# Ethernet_PHY.net
KiCad netlist of a schematic drawn in Altium Designer
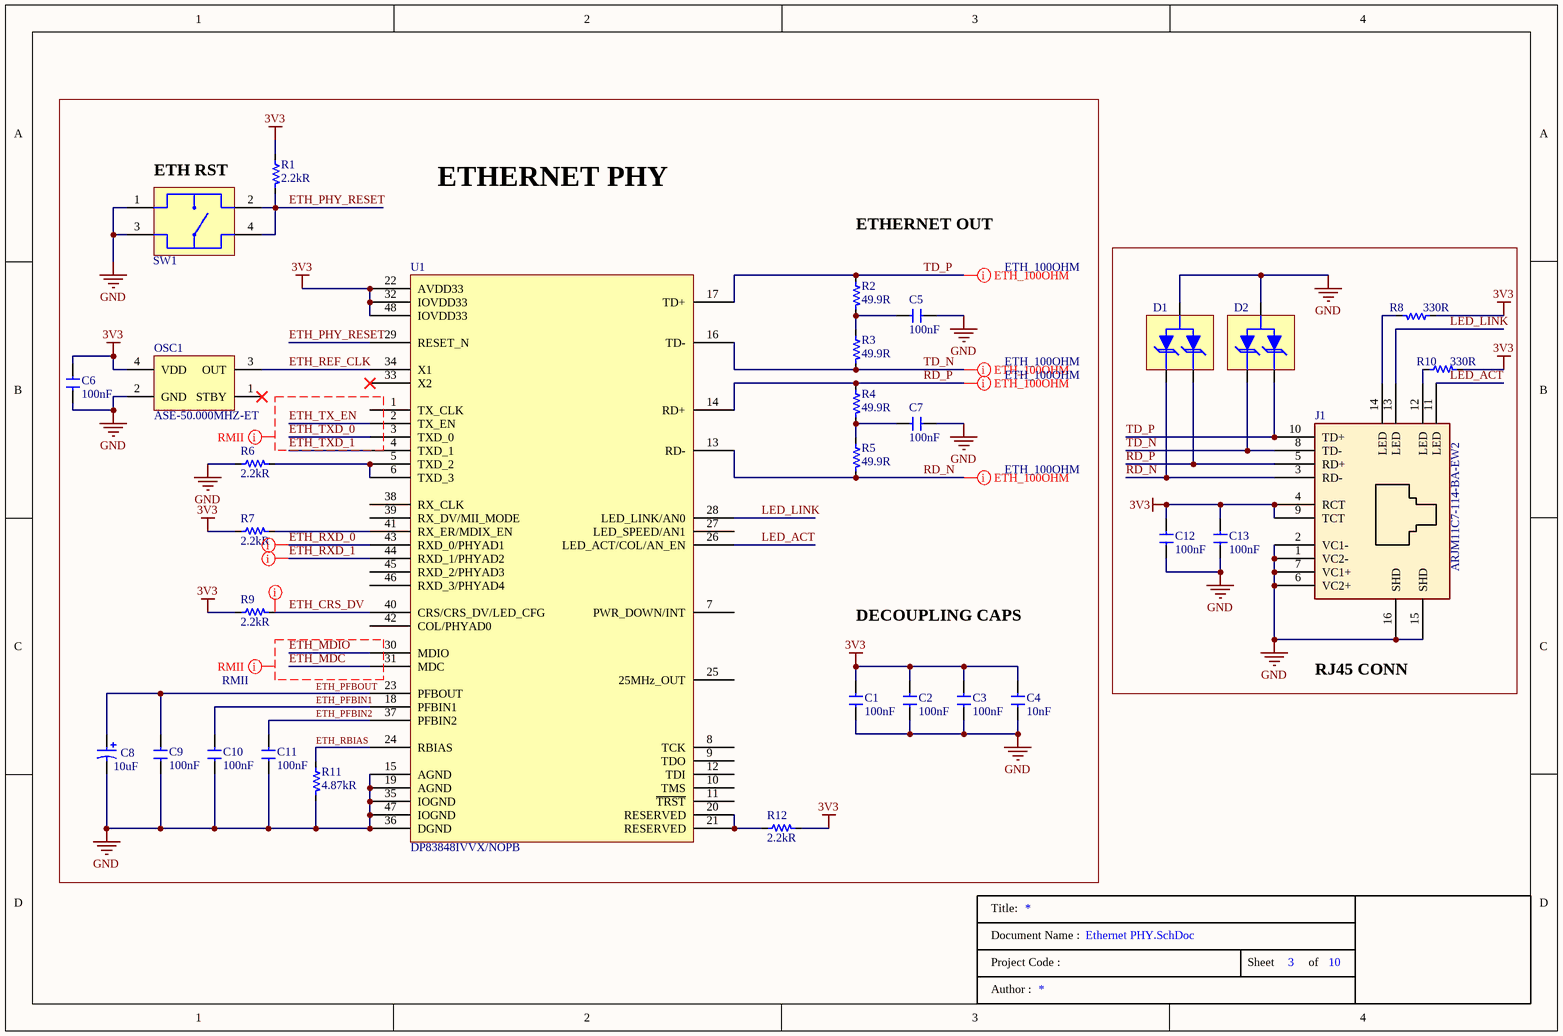
[diagram p0: Ethernet PHY.SchDoc]

(export (version "E")
  (design (tool "Eeschema 10.0.6"))
  (components
    (comp (ref "C1")
      (value "CAP_0.1uF_%20_50V_0805_X7R_CER")
      (footprint "0805_CAP")
      (description "Cap Ceramic 0.1uF 50V X7R 20% SMD 0805 125C Paper T/R")
      (fields
        (field (name "MANUFACTURER") "KEMET")
        (field (name "MANUFACTURER PART NUMBER") "C0805C104M5RACTU")
        (field (name "CAPACITANCE") "100nF")
      )
      (libsource (lib "Main Schematic Library") (part "CAP_0.1uF_%20_50V_0805_X7R_CER"))
    )
    (comp (ref "C2")
      (value "CAP_0.1uF_%20_50V_0805_X7R_CER")
      (footprint "0805_CAP")
      (description "Cap Ceramic 0.1uF 50V X7R 20% SMD 0805 125C Paper T/R")
      (fields
        (field (name "MANUFACTURER") "KEMET")
        (field (name "MANUFACTURER PART NUMBER") "C0805C104M5RACTU")
        (field (name "CAPACITANCE") "100nF")
      )
      (libsource (lib "Main Schematic Library") (part "CAP_0.1uF_%20_50V_0805_X7R_CER"))
    )
    (comp (ref "C3")
      (value "CAP_0.1uF_%20_50V_0805_X7R_CER")
      (footprint "0805_CAP")
      (description "Cap Ceramic 0.1uF 50V X7R 20% SMD 0805 125C Paper T/R")
      (fields
        (field (name "MANUFACTURER") "KEMET")
        (field (name "MANUFACTURER PART NUMBER") "C0805C104M5RACTU")
        (field (name "CAPACITANCE") "100nF")
      )
      (libsource (lib "Main Schematic Library") (part "CAP_0.1uF_%20_50V_0805_X7R_CER"))
    )
    (comp (ref "C4")
      (value "CAP_10nF_%10_50V_0805_X7R_CER")
      (footprint "0805_CAP")
      (description "CAP CER 10000PF 50V X7R 0805")
      (fields
        (field (name "MANUFACTURER") "Samsung")
        (field (name "MANUFACTURER PART NUMBER") "CL21B103KBANNNC")
        (field (name "CAPACITANCE") "10nF")
      )
      (libsource (lib "Main Schematic Library") (part "CAP_10nF_%10_50V_0805_X7R_CER"))
    )
    (comp (ref "C5")
      (value "CAP_0.1uF_50V_0805_X7R_CER")
      (footprint "0805_CAP")
      (description "Cap Ceramic 0.1uF 50V X7R 20% SMD 0805 125C Paper T/R")
      (fields
        (field (name "MANUFACTURER") "KEMET")
        (field (name "MANUFACTURER PART NUMBER") "C0805C104M5RACTU")
        (field (name "CAPACITANCE") "100nF")
      )
      (libsource (lib "Main Component Library") (part "CAP_0.1uF_50V_0805_X7R_CER"))
    )
    (comp (ref "C6")
      (value "CAP_0.1uF_50V_0805_X7R_CER")
      (footprint "0805_CAP")
      (description "Cap Ceramic 0.1uF 50V X7R 20% SMD 0805 125C Paper T/R")
      (fields
        (field (name "MANUFACTURER") "KEMET")
        (field (name "MANUFACTURER PART NUMBER") "C0805C104M5RACTU")
        (field (name "CAPACITANCE") "100nF")
      )
      (libsource (lib "Main Component Library") (part "CAP_0.1uF_50V_0805_X7R_CER"))
    )
    (comp (ref "C7")
      (value "CAP_0.1uF_50V_0805_X7R_CER")
      (footprint "0805_CAP")
      (description "Cap Ceramic 0.1uF 50V X7R 20% SMD 0805 125C Paper T/R")
      (fields
        (field (name "MANUFACTURER") "KEMET")
        (field (name "MANUFACTURER PART NUMBER") "C0805C104M5RACTU")
        (field (name "CAPACITANCE") "100nF")
      )
      (libsource (lib "Main Component Library") (part "CAP_0.1uF_50V_0805_X7R_CER"))
    )
    (comp (ref "C8")
      (value "CAP_10uF_10V_10%_1206_TANT")
      (footprint "1206_TANT_CAP")
      (description "Cap Tant Solid 10uF 10V A CASE 10% (3.2 X 1.6 X 1.6mm) Inward L SMD 3216-18 3 Ohm 125C T/R")
      (fields
        (field (name "MANUFACTURER") "Kyocera AVX")
        (field (name "MANUFACTURER PART NUMBER") "TAJA106K010SNJ")
        (field (name "CAPACITANCE") "10uF")
      )
      (libsource (lib "Main Component Library") (part "CAP_10uF_10V_10%_1206_TANT"))
    )
    (comp (ref "C9")
      (value "CAP_0.1uF_%20_50V_0805_X7R_CER")
      (footprint "0805_CAP")
      (description "Cap Ceramic 0.1uF 50V X7R 20% SMD 0805 125C Paper T/R")
      (fields
        (field (name "MANUFACTURER") "KEMET")
        (field (name "MANUFACTURER PART NUMBER") "C0805C104M5RACTU")
        (field (name "CAPACITANCE") "100nF")
      )
      (libsource (lib "Main Schematic Library") (part "CAP_0.1uF_%20_50V_0805_X7R_CER"))
    )
    (comp (ref "C10")
      (value "CAP_0.1uF_%20_50V_0805_X7R_CER")
      (footprint "0805_CAP")
      (description "Cap Ceramic 0.1uF 50V X7R 20% SMD 0805 125C Paper T/R")
      (fields
        (field (name "MANUFACTURER") "KEMET")
        (field (name "MANUFACTURER PART NUMBER") "C0805C104M5RACTU")
        (field (name "CAPACITANCE") "100nF")
      )
      (libsource (lib "Main Schematic Library") (part "CAP_0.1uF_%20_50V_0805_X7R_CER"))
    )
    (comp (ref "C11")
      (value "CAP_0.1uF_%20_50V_0805_X7R_CER")
      (footprint "0805_CAP")
      (description "Cap Ceramic 0.1uF 50V X7R 20% SMD 0805 125C Paper T/R")
      (fields
        (field (name "MANUFACTURER") "KEMET")
        (field (name "MANUFACTURER PART NUMBER") "C0805C104M5RACTU")
        (field (name "CAPACITANCE") "100nF")
      )
      (libsource (lib "Main Schematic Library") (part "CAP_0.1uF_%20_50V_0805_X7R_CER"))
    )
    (comp (ref "C12")
      (value "CAP_0.1uF_50V_0805_X7R_CER")
      (footprint "0805_CAP")
      (description "Cap Ceramic 0.1uF 50V X7R 20% SMD 0805 125C Paper T/R")
      (fields
        (field (name "MANUFACTURER") "KEMET")
        (field (name "MANUFACTURER PART NUMBER") "C0805C104M5RACTU")
        (field (name "CAPACITANCE") "100nF")
      )
      (libsource (lib "Main Component Library") (part "CAP_0.1uF_50V_0805_X7R_CER"))
    )
    (comp (ref "C13")
      (value "CAP_0.1uF_50V_0805_X7R_CER")
      (footprint "0805_CAP")
      (description "Cap Ceramic 0.1uF 50V X7R 20% SMD 0805 125C Paper T/R")
      (fields
        (field (name "MANUFACTURER") "KEMET")
        (field (name "MANUFACTURER PART NUMBER") "C0805C104M5RACTU")
        (field (name "CAPACITANCE") "100nF")
      )
      (libsource (lib "Main Component Library") (part "CAP_0.1uF_50V_0805_X7R_CER"))
    )
    (comp (ref "D1")
      (value "DIODE_TVS_3.3VWM_8VC_SOT23")
      (footprint "SOT170P237X110-3N")
      (description "ESD Suppressor TVS Uni-Dir 3.3V 3-Pin SOT-23 T/R")
      (fields (field (name "MANUFACTURER") "MCC") (field (name "MANUFACTURER PART NUMBER") "ESD3V3AP-TP"))
      (libsource (lib "Main Schematic Library") (part "DIODE_TVS_3.3VWM_8VC_SOT23"))
    )
    (comp (ref "D2")
      (value "DIODE_TVS_3.3VWM_8VC_SOT23")
      (footprint "SOT170P237X110-3N")
      (description "ESD Suppressor TVS Uni-Dir 3.3V 3-Pin SOT-23 T/R")
      (fields (field (name "MANUFACTURER") "MCC") (field (name "MANUFACTURER PART NUMBER") "ESD3V3AP-TP"))
      (libsource (lib "Main Schematic Library") (part "DIODE_TVS_3.3VWM_8VC_SOT23"))
    )
    (comp (ref "J1")
      (value "ARJM11C7-114-BA-EW2")
      (footprint "ARJM11C7-114-BA-EW2_ABR")
      (description "Conn RJ-45 F 8 POS 1.27mm Solder RA Thru-Hole 14 Terminal 1 Port Tray")
      (fields (field (name "MANUFACTURER") "Abracon"))
      (libsource (lib "Main Schematic Library") (part "CONN_RJ-45_JACK_1PORT 100 BASE-T PoE_w/LED"))
    )
    (comp (ref "OSC1")
      (value "ASE-50.000MHZ-ET")
      (footprint "4-SMD_CMOS_OSC_3.20MMX2.50")
      (description "3.2 X 2.5 X 1.1Mm, 3.3V , 100Ppm -20+70C, Smd Ceramic Oscillator Rohs Compliant: Yes")
      (fields (field (name "MANUFACTURER") "Abracon"))
      (libsource (lib "Main Component Library") (part "XTAL_OSC_XO_50.0000MHZ_CMOS_SMD"))
    )
    (comp (ref "R1")
      (value "RES_2.2K OHM_1%_0805_1/8W")
      (footprint "0805_RES")
      (description "Res Thick Film 0805 2.2K Ohm 1% 1/8W ±100ppm/°C SMD Paper T/R")
      (fields
        (field (name "MANUFACTURER") "Yageo")
        (field (name "MANUFACTURER PART NUMBER") "RC0805FR-132K2L")
        (field (name "RESISTANCE") "2.2kR")
      )
      (libsource (lib "Main Component Library") (part "RES_2.2K OHM_1%_0805_1/8W"))
    )
    (comp (ref "R2")
      (value "RES_49.9 OHM_1%_0603_1/10W")
      (footprint "0603_RES")
      (description "Res Thick Film 0603 49.9 Ohm 1% 1/10W ±100ppm/°C Molded SMD Paper T/R")
      (fields
        (field (name "MANUFACTURER") "Vishay")
        (field (name "MANUFACTURER PART NUMBER") "CRCW060349R9FKEAC")
        (field (name "RESISTANCE") "49.9R")
      )
      (libsource (lib "Main Component Library") (part "RES_49.9 OHM_1%_0603_1/10W"))
    )
    (comp (ref "R3")
      (value "RES_49.9 OHM_1%_0603_1/10W")
      (footprint "0603_RES")
      (description "Res Thick Film 0603 49.9 Ohm 1% 1/10W ±100ppm/°C Molded SMD Paper T/R")
      (fields
        (field (name "MANUFACTURER") "Vishay")
        (field (name "MANUFACTURER PART NUMBER") "CRCW060349R9FKEAC")
        (field (name "RESISTANCE") "49.9R")
      )
      (libsource (lib "Main Component Library") (part "RES_49.9 OHM_1%_0603_1/10W"))
    )
    (comp (ref "R4")
      (value "RES_49.9 OHM_1%_0603_1/10W")
      (footprint "0603_RES")
      (description "Res Thick Film 0603 49.9 Ohm 1% 1/10W ±100ppm/°C Molded SMD Paper T/R")
      (fields
        (field (name "MANUFACTURER") "Vishay")
        (field (name "MANUFACTURER PART NUMBER") "CRCW060349R9FKEAC")
        (field (name "RESISTANCE") "49.9R")
      )
      (libsource (lib "Main Component Library") (part "RES_49.9 OHM_1%_0603_1/10W"))
    )
    (comp (ref "R5")
      (value "RES_49.9 OHM_1%_0603_1/10W")
      (footprint "0603_RES")
      (description "Res Thick Film 0603 49.9 Ohm 1% 1/10W ±100ppm/°C Molded SMD Paper T/R")
      (fields
        (field (name "MANUFACTURER") "Vishay")
        (field (name "MANUFACTURER PART NUMBER") "CRCW060349R9FKEAC")
        (field (name "RESISTANCE") "49.9R")
      )
      (libsource (lib "Main Component Library") (part "RES_49.9 OHM_1%_0603_1/10W"))
    )
    (comp (ref "R6")
      (value "RES_2.2K OHM_1%_0805_1/8W")
      (footprint "0805_RES")
      (description "Res Thick Film 0805 2.2K Ohm 1% 1/8W ±100ppm/°C SMD Paper T/R")
      (fields
        (field (name "MANUFACTURER") "Yageo")
        (field (name "MANUFACTURER PART NUMBER") "RC0805FR-132K2L")
        (field (name "RESISTANCE") "2.2kR")
      )
      (libsource (lib "Main Component Library") (part "RES_2.2K OHM_1%_0805_1/8W"))
    )
    (comp (ref "R7")
      (value "RES_2.2K OHM_1%_0805_1/8W")
      (footprint "0805_RES")
      (description "Res Thick Film 0805 2.2K Ohm 1% 1/8W ±100ppm/°C SMD Paper T/R")
      (fields
        (field (name "MANUFACTURER") "Yageo")
        (field (name "MANUFACTURER PART NUMBER") "RC0805FR-132K2L")
        (field (name "RESISTANCE") "2.2kR")
      )
      (libsource (lib "Main Component Library") (part "RES_2.2K OHM_1%_0805_1/8W"))
    )
    (comp (ref "R8")
      (value "RES_330 OHM_5%_0805_1/8W")
      (footprint "0805_RES")
      (description "Res Thick Film 0805 330 Ohm 5% 0.125W(1/8W) ±100ppm/C Pad SMD Automotive T/R")
      (fields
        (field (name "MANUFACTURER") "TE Connectivity")
        (field (name "MANUFACTURER PART NUMBER") "CRGCQ0805J330R")
        (field (name "RESISTANCE") "330R")
      )
      (libsource (lib "Main Component Library") (part "RES_330 OHM_5%_0805_1/8W"))
    )
    (comp (ref "R9")
      (value "RES_2.2K OHM_1%_0805_1/8W")
      (footprint "0805_RES")
      (description "Res Thick Film 0805 2.2K Ohm 1% 1/8W ±100ppm/°C SMD Paper T/R")
      (fields
        (field (name "MANUFACTURER") "Yageo")
        (field (name "MANUFACTURER PART NUMBER") "RC0805FR-132K2L")
        (field (name "RESISTANCE") "2.2kR")
      )
      (libsource (lib "Main Component Library") (part "RES_2.2K OHM_1%_0805_1/8W"))
    )
    (comp (ref "R10")
      (value "RES_330 OHM_5%_0805_1/8W")
      (footprint "0805_RES")
      (description "Res Thick Film 0805 330 Ohm 5% 0.125W(1/8W) ±100ppm/C Pad SMD Automotive T/R")
      (fields
        (field (name "MANUFACTURER") "TE Connectivity")
        (field (name "MANUFACTURER PART NUMBER") "CRGCQ0805J330R")
        (field (name "RESISTANCE") "330R")
      )
      (libsource (lib "Main Component Library") (part "RES_330 OHM_5%_0805_1/8W"))
    )
    (comp (ref "R11")
      (value "RES_4.87K_OHM_1%_1/8W 0805")
      (footprint "0805_RES")
      (description "Res Thick Film 0805 4.87K Ohm 1% 1/8W ±100ppm/°C SMD Paper T/R")
      (fields
        (field (name "MANUFACTURER") "Yageo")
        (field (name "MANUFACTURER PART NUMBER") "RC0805FR-074K87L")
        (field (name "RESISTANCE") "4.87kR")
      )
      (libsource (lib "Main Schematic Library") (part "RES_4.87K_OHM_1%_1/8W 0805"))
    )
    (comp (ref "R12")
      (value "RES_2.2K OHM_1%_0805_1/8W")
      (footprint "0805_RES")
      (description "Res Thick Film 0805 2.2K Ohm 1% 1/8W ±100ppm/°C SMD Paper T/R")
      (fields
        (field (name "MANUFACTURER") "Yageo")
        (field (name "MANUFACTURER PART NUMBER") "RC0805FR-132K2L")
        (field (name "RESISTANCE") "2.2kR")
      )
      (libsource (lib "Main Component Library") (part "RES_2.2K OHM_1%_0805_1/8W"))
    )
    (comp (ref "SW1")
      (value "SWITCH_TACTILE_SPST-NO_0.05A_12V")
      (footprint "TACT_SWITCH_6MMX6MM")
      (description "Switch Tactile N.O. SPST Round Button Gull Wing 0.05A 12VDC 100000Cycles 1.27N SMD T/R")
      (fields
        (field (name "MANUFACTURER") "ITT C&K")
        (field (name "MANUFACTURER PART NUMBER") "PTS645SL43SMTR92LFS")
      )
      (libsource (lib "Main Component Library") (part "SWITCH_TACTILE_SPST-NO_0.05A_12V"))
    )
    (comp (ref "U1")
      (value "DP83848IVVX/NOPB")
      (footprint "TSQFP50P900X900X160-48N")
      (description "1/1 Transceiver  Ethernet 48-LQFP (7x7)")
      (fields (field (name "MANUFACTURER") "TI National Semiconductor"))
      (libsource (lib "Main Component Library") (part "IC_PHY_DP83848I"))
    )
  )
  (nets
    (net (code "1") (name "/ETH_CRS_DV") (class "Default")
      (node (ref "R9") (pin "1") (pinfunction "1_1") (pintype "passive"))
      (node (ref "U1") (pin "40") (pinfunction "CRS/CRS_DV/LED_CFG_40") (pintype "passive"))
    )
    (net (code "2") (name "/ETH_MDC") (class "Default")
      (node (ref "U1") (pin "31") (pinfunction "MDC_31") (pintype "passive"))
    )
    (net (code "3") (name "/ETH_MDIO") (class "Default")
      (node (ref "U1") (pin "30") (pinfunction "MDIO_30") (pintype "passive"))
    )
    (net (code "4") (name "/ETH_PFBIN1") (class "Default")
      (node (ref "C10") (pin "2") (pinfunction "2_2") (pintype "passive"))
      (node (ref "U1") (pin "18") (pinfunction "PFBIN1_18") (pintype "passive"))
    )
    (net (code "5") (name "/ETH_PFBIN2") (class "Default")
      (node (ref "C11") (pin "2") (pinfunction "2_2") (pintype "passive"))
      (node (ref "U1") (pin "37") (pinfunction "PFBIN2_37") (pintype "passive"))
    )
    (net (code "6") (name "/ETH_PFBOUT") (class "Default")
      (node (ref "C8") (pin "1") (pinfunction "1_1") (pintype "passive"))
      (node (ref "C9") (pin "2") (pinfunction "2_2") (pintype "passive"))
      (node (ref "U1") (pin "23") (pinfunction "PFBOUT_23") (pintype "passive"))
    )
    (net (code "7") (name "/ETH_PHY_RESET") (class "Default")
      (node (ref "R1") (pin "1") (pinfunction "1_1") (pintype "passive"))
      (node (ref "SW1") (pin "2") (pinfunction "2_2") (pintype "passive"))
      (node (ref "SW1") (pin "4") (pinfunction "4_4") (pintype "passive"))
      (node (ref "U1") (pin "29") (pinfunction "RESET_N_29") (pintype "passive"))
    )
    (net (code "8") (name "/ETH_RBIAS") (class "Default")
      (node (ref "R11") (pin "2") (pinfunction "2_2") (pintype "passive"))
      (node (ref "U1") (pin "24") (pinfunction "RBIAS_24") (pintype "passive"))
    )
    (net (code "9") (name "/ETH_REF_CLK") (class "Default")
      (node (ref "OSC1") (pin "3") (pinfunction "OUT_3") (pintype "passive"))
      (node (ref "U1") (pin "34") (pinfunction "X1_34") (pintype "passive"))
    )
    (net (code "10") (name "/ETH_RXD_0") (class "Default")
      (node (ref "U1") (pin "43") (pinfunction "RXD_0/PHYAD1_43") (pintype "passive"))
    )
    (net (code "11") (name "/ETH_RXD_1") (class "Default")
      (node (ref "U1") (pin "44") (pinfunction "RXD_1/PHYAD2_44") (pintype "passive"))
    )
    (net (code "12") (name "/ETH_TXD_0") (class "Default")
      (node (ref "U1") (pin "3") (pinfunction "TXD_0_3") (pintype "passive"))
    )
    (net (code "13") (name "/ETH_TXD_1") (class "Default")
      (node (ref "U1") (pin "4") (pinfunction "TXD_1_4") (pintype "passive"))
    )
    (net (code "14") (name "/ETH_TX_EN") (class "Default")
      (node (ref "U1") (pin "2") (pinfunction "TX_EN_2") (pintype "passive"))
    )
    (net (code "15") (name "/LED_ACT") (class "Default")
      (node (ref "J1") (pin "11") (pinfunction "LED_11") (pintype "passive"))
      (node (ref "U1") (pin "26") (pinfunction "LED_ACT/COL/AN_EN_26") (pintype "passive"))
    )
    (net (code "16") (name "/LED_LINK") (class "Default")
      (node (ref "J1") (pin "13") (pinfunction "LED_13") (pintype "passive"))
      (node (ref "U1") (pin "28") (pinfunction "LED_LINK/AN0_28") (pintype "passive"))
    )
    (net (code "17") (name "/RD_N") (class "Default")
      (node (ref "D1") (pin "1") (pinfunction "CATHODE_1_1") (pintype "passive"))
      (node (ref "J1") (pin "3") (pinfunction "RD-_3") (pintype "passive"))
      (node (ref "R5") (pin "1") (pinfunction "1_1") (pintype "passive"))
      (node (ref "U1") (pin "13") (pinfunction "RD-_13") (pintype "passive"))
    )
    (net (code "18") (name "/RD_P") (class "Default")
      (node (ref "D1") (pin "2") (pinfunction "CATHODE_2_2") (pintype "passive"))
      (node (ref "J1") (pin "5") (pinfunction "RD+_5") (pintype "passive"))
      (node (ref "R4") (pin "2") (pinfunction "2_2") (pintype "passive"))
      (node (ref "U1") (pin "14") (pinfunction "RD+_14") (pintype "passive"))
    )
    (net (code "19") (name "/TD_N") (class "Default")
      (node (ref "D2") (pin "1") (pinfunction "CATHODE_1_1") (pintype "passive"))
      (node (ref "J1") (pin "8") (pinfunction "TD-_8") (pintype "passive"))
      (node (ref "R3") (pin "1") (pinfunction "1_1") (pintype "passive"))
      (node (ref "U1") (pin "16") (pinfunction "TD-_16") (pintype "passive"))
    )
    (net (code "20") (name "/TD_P") (class "Default")
      (node (ref "D2") (pin "2") (pinfunction "CATHODE_2_2") (pintype "passive"))
      (node (ref "J1") (pin "10") (pinfunction "TD+_10") (pintype "passive"))
      (node (ref "R2") (pin "2") (pinfunction "2_2") (pintype "passive"))
      (node (ref "U1") (pin "17") (pinfunction "TD+_17") (pintype "passive"))
    )
    (net (code "21") (name "3V3") (class "Default")
      (node (ref "C1") (pin "2") (pinfunction "2_2") (pintype "passive"))
      (node (ref "C12") (pin "1") (pinfunction "1_1") (pintype "passive"))
      (node (ref "C13") (pin "1") (pinfunction "1_1") (pintype "passive"))
      (node (ref "C2") (pin "2") (pinfunction "2_2") (pintype "passive"))
      (node (ref "C3") (pin "2") (pinfunction "2_2") (pintype "passive"))
      (node (ref "C4") (pin "2") (pinfunction "2_2") (pintype "passive"))
      (node (ref "C6") (pin "2") (pinfunction "2_2") (pintype "passive"))
      (node (ref "J1") (pin "4") (pinfunction "RCT_4") (pintype "passive"))
      (node (ref "J1") (pin "9") (pinfunction "TCT_9") (pintype "passive"))
      (node (ref "OSC1") (pin "4") (pinfunction "VDD_4") (pintype "passive"))
      (node (ref "R1") (pin "2") (pinfunction "2_2") (pintype "passive"))
      (node (ref "R10") (pin "1") (pinfunction "1_1") (pintype "passive"))
      (node (ref "R12") (pin "1") (pinfunction "1_1") (pintype "passive"))
      (node (ref "R7") (pin "2") (pinfunction "2_2") (pintype "passive"))
      (node (ref "R8") (pin "2") (pinfunction "2_2") (pintype "passive"))
      (node (ref "R9") (pin "2") (pinfunction "2_2") (pintype "passive"))
      (node (ref "U1") (pin "22") (pinfunction "AVDD33_22") (pintype "passive"))
      (node (ref "U1") (pin "32") (pinfunction "IOVDD33_32") (pintype "passive"))
      (node (ref "U1") (pin "48") (pinfunction "IOVDD33_48") (pintype "passive"))
    )
    (net (code "22") (name "GND") (class "Default")
      (node (ref "C1") (pin "1") (pinfunction "1_1") (pintype "passive"))
      (node (ref "C10") (pin "1") (pinfunction "1_1") (pintype "passive"))
      (node (ref "C11") (pin "1") (pinfunction "1_1") (pintype "passive"))
      (node (ref "C12") (pin "2") (pinfunction "2_2") (pintype "passive"))
      (node (ref "C13") (pin "2") (pinfunction "2_2") (pintype "passive"))
      (node (ref "C2") (pin "1") (pinfunction "1_1") (pintype "passive"))
      (node (ref "C3") (pin "1") (pinfunction "1_1") (pintype "passive"))
      (node (ref "C4") (pin "1") (pinfunction "1_1") (pintype "passive"))
      (node (ref "C5") (pin "1") (pinfunction "1_1") (pintype "passive"))
      (node (ref "C6") (pin "1") (pinfunction "1_1") (pintype "passive"))
      (node (ref "C7") (pin "1") (pinfunction "1_1") (pintype "passive"))
      (node (ref "C8") (pin "2") (pinfunction "2_2") (pintype "passive"))
      (node (ref "C9") (pin "1") (pinfunction "1_1") (pintype "passive"))
      (node (ref "D1") (pin "3") (pinfunction "ANODE_3") (pintype "passive"))
      (node (ref "D2") (pin "3") (pinfunction "ANODE_3") (pintype "passive"))
      (node (ref "J1") (pin "1") (pinfunction "VC2-_1") (pintype "power_in"))
      (node (ref "J1") (pin "15") (pinfunction "SHD_15") (pintype "passive"))
      (node (ref "J1") (pin "16") (pinfunction "SHD_16") (pintype "passive"))
      (node (ref "J1") (pin "2") (pinfunction "VC1-_2") (pintype "power_in"))
      (node (ref "J1") (pin "6") (pinfunction "VC2+_6") (pintype "power_in"))
      (node (ref "J1") (pin "7") (pinfunction "VC1+_7") (pintype "power_in"))
      (node (ref "OSC1") (pin "2") (pinfunction "GND_2") (pintype "passive"))
      (node (ref "R11") (pin "1") (pinfunction "1_1") (pintype "passive"))
      (node (ref "R6") (pin "2") (pinfunction "2_2") (pintype "passive"))
      (node (ref "SW1") (pin "1") (pinfunction "1_1") (pintype "passive"))
      (node (ref "SW1") (pin "3") (pinfunction "3_3") (pintype "passive"))
      (node (ref "U1") (pin "15") (pinfunction "AGND_15") (pintype "passive"))
      (node (ref "U1") (pin "19") (pinfunction "AGND_19") (pintype "passive"))
      (node (ref "U1") (pin "35") (pinfunction "IOGND_35") (pintype "passive"))
      (node (ref "U1") (pin "36") (pinfunction "DGND_36") (pintype "passive"))
      (node (ref "U1") (pin "47") (pinfunction "IOGND_47") (pintype "passive"))
    )
    (net (code "23") (name "Net-(C5-Pad2)") (class "Default")
      (node (ref "C5") (pin "2") (pinfunction "2_2") (pintype "passive"))
      (node (ref "R2") (pin "1") (pinfunction "1_1") (pintype "passive"))
      (node (ref "R3") (pin "2") (pinfunction "2_2") (pintype "passive"))
    )
    (net (code "24") (name "Net-(C7-Pad2)") (class "Default")
      (node (ref "C7") (pin "2") (pinfunction "2_2") (pintype "passive"))
      (node (ref "R4") (pin "1") (pinfunction "1_1") (pintype "passive"))
      (node (ref "R5") (pin "2") (pinfunction "2_2") (pintype "passive"))
    )
    (net (code "25") (name "Net-(J1-LED-Pad12)") (class "Default")
      (node (ref "J1") (pin "12") (pinfunction "LED_12") (pintype "passive"))
      (node (ref "R10") (pin "2") (pinfunction "2_2") (pintype "passive"))
    )
    (net (code "26") (name "Net-(J1-LED-Pad14)") (class "Default")
      (node (ref "J1") (pin "14") (pinfunction "LED_14") (pintype "passive"))
      (node (ref "R8") (pin "1") (pinfunction "1_1") (pintype "passive"))
    )
    (net (code "27") (name "Net-(R12-Pad2)") (class "Default")
      (node (ref "R12") (pin "2") (pinfunction "2_2") (pintype "passive"))
      (node (ref "U1") (pin "20") (pinfunction "RESERVED_20") (pintype "passive"))
      (node (ref "U1") (pin "21") (pinfunction "RESERVED_21") (pintype "passive"))
    )
    (net (code "28") (name "Net-(U1-RX_ER{slash}MDIX_EN)") (class "Default")
      (node (ref "R7") (pin "1") (pinfunction "1_1") (pintype "passive"))
      (node (ref "U1") (pin "41") (pinfunction "RX_ER/MDIX_EN_41") (pintype "passive"))
    )
    (net (code "29") (name "Net-(U1-TXD_2)") (class "Default")
      (node (ref "R6") (pin "1") (pinfunction "1_1") (pintype "passive"))
      (node (ref "U1") (pin "5") (pinfunction "TXD_2_5") (pintype "passive"))
      (node (ref "U1") (pin "6") (pinfunction "TXD_3_6") (pintype "passive"))
    )
    (net (code "30") (name "unconnected-(OSC1-STBY-Pad1)") (class "Default")
      (node (ref "OSC1") (pin "1") (pinfunction "STBY_1") (pintype "passive+no_connect"))
    )
    (net (code "31") (name "unconnected-(U1-25MHz_OUT-Pad25)") (class "Default")
      (node (ref "U1") (pin "25") (pinfunction "25MHz_OUT_25") (pintype "passive"))
    )
    (net (code "32") (name "unconnected-(U1-COL{slash}PHYAD0-Pad42)") (class "Default")
      (node (ref "U1") (pin "42") (pinfunction "COL/PHYAD0_42") (pintype "passive"))
    )
    (net (code "33") (name "unconnected-(U1-LED_SPEED{slash}AN1-Pad27)") (class "Default")
      (node (ref "U1") (pin "27") (pinfunction "LED_SPEED/AN1_27") (pintype "passive"))
    )
    (net (code "34") (name "unconnected-(U1-PWR_DOWN{slash}INT-Pad7)") (class "Default")
      (node (ref "U1") (pin "7") (pinfunction "PWR_DOWN/INT_7") (pintype "passive"))
    )
    (net (code "35") (name "unconnected-(U1-RXD_2{slash}PHYAD3-Pad45)") (class "Default")
      (node (ref "U1") (pin "45") (pinfunction "RXD_2/PHYAD3_45") (pintype "passive"))
    )
    (net (code "36") (name "unconnected-(U1-RXD_3{slash}PHYAD4-Pad46)") (class "Default")
      (node (ref "U1") (pin "46") (pinfunction "RXD_3/PHYAD4_46") (pintype "passive"))
    )
    (net (code "37") (name "unconnected-(U1-RX_CLK-Pad38)") (class "Default")
      (node (ref "U1") (pin "38") (pinfunction "RX_CLK_38") (pintype "passive"))
    )
    (net (code "38") (name "unconnected-(U1-RX_DV{slash}MII_MODE-Pad39)") (class "Default")
      (node (ref "U1") (pin "39") (pinfunction "RX_DV/MII_MODE_39") (pintype "passive"))
    )
    (net (code "39") (name "unconnected-(U1-TCK-Pad8)") (class "Default")
      (node (ref "U1") (pin "8") (pinfunction "TCK_8") (pintype "passive"))
    )
    (net (code "40") (name "unconnected-(U1-TDI-Pad12)") (class "Default")
      (node (ref "U1") (pin "12") (pinfunction "TDI_12") (pintype "passive"))
    )
    (net (code "41") (name "unconnected-(U1-TDO-Pad9)") (class "Default")
      (node (ref "U1") (pin "9") (pinfunction "TDO_9") (pintype "passive"))
    )
    (net (code "42") (name "unconnected-(U1-TMS-Pad10)") (class "Default")
      (node (ref "U1") (pin "10") (pinfunction "TMS_10") (pintype "passive"))
    )
    (net (code "43") (name "unconnected-(U1-TX_CLK-Pad1)") (class "Default")
      (node (ref "U1") (pin "1") (pinfunction "TX_CLK_1") (pintype "passive"))
    )
    (net (code "44") (name "unconnected-(U1-X2-Pad33)") (class "Default")
      (node (ref "U1") (pin "33") (pinfunction "X2_33") (pintype "passive+no_connect"))
    )
    (net (code "45") (name "unconnected-(U1-~{TRST}-Pad11)") (class "Default")
      (node (ref "U1") (pin "11") (pinfunction "~{TRST}_11") (pintype "passive"))
    )
  )
)
